# Microcontroller.net
KiCad netlist of a schematic drawn in Altium Designer
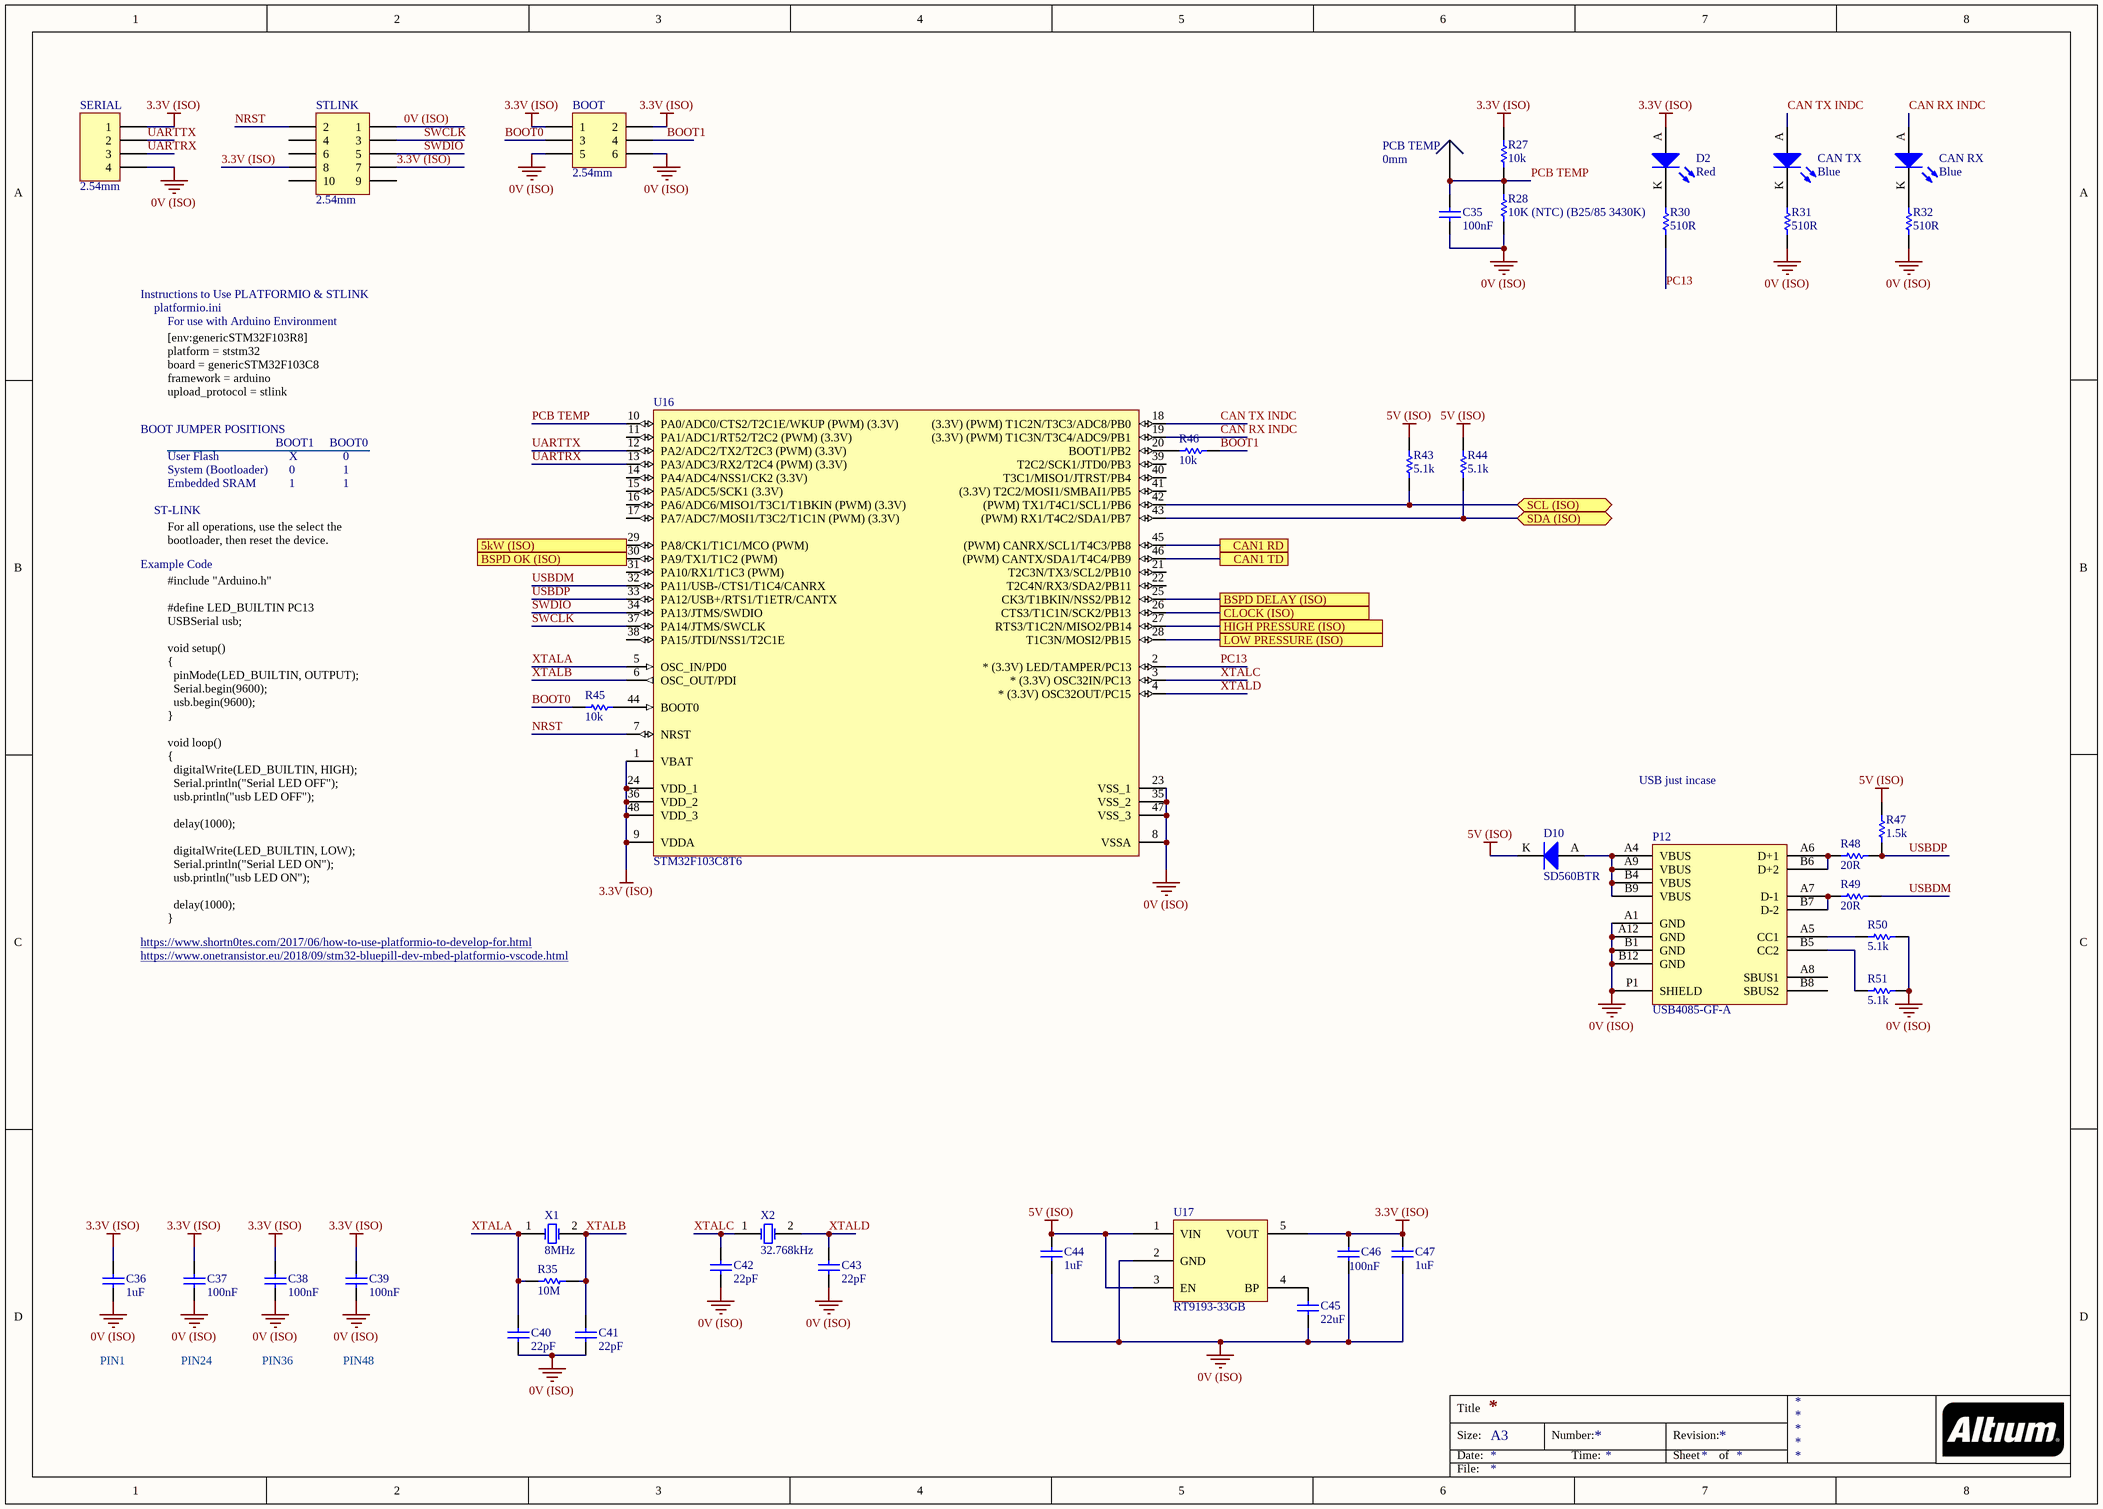
[diagram p0: Microcontroller.SchDoc]

(export (version "E")
  (design (tool "Eeschema 10.0.6"))
  (components
    (comp (ref "BOOT")
      (value "2.54mm")
      (footprint "TH 2.54mm Header 2x3")
      (fields (field (name "PART NUMBER") "TH 2.54mm Header 2x3") (field (name "CONTACT") "NA"))
      (libsource (lib "ts_20-standard-connectors") (part "Header 2x3"))
    )
    (comp (ref "C35")
      (value "100nF")
      (footprint "0805")
      (fields
        (field (name "PART NUMBER") "GCM21BR71E104KA37L")
        (field (name "TOLERANCE") "10%")
        (field (name "MANUFACTURER") "muRata")
      )
      (libsource (lib "ts_20-standard-library") (part "Capacitor"))
    )
    (comp (ref "C36")
      (value "1uF")
      (footprint "0805")
      (fields
        (field (name "PART NUMBER") "AC0805KKX7R8BB105")
        (field (name "TOLERANCE") "10%")
        (field (name "MANUFACTURER") "YAGEO")
      )
      (libsource (lib "ts_20-standard-library") (part "Capacitor"))
    )
    (comp (ref "C37")
      (value "100nF")
      (footprint "0805")
      (fields
        (field (name "PART NUMBER") "GCM21BR71E104KA37L")
        (field (name "TOLERANCE") "10%")
        (field (name "MANUFACTURER") "muRata")
      )
      (libsource (lib "ts_20-standard-library") (part "Capacitor"))
    )
    (comp (ref "C38")
      (value "100nF")
      (footprint "0805")
      (fields
        (field (name "PART NUMBER") "GCM21BR71E104KA37L")
        (field (name "TOLERANCE") "10%")
        (field (name "MANUFACTURER") "muRata")
      )
      (libsource (lib "ts_20-standard-library") (part "Capacitor"))
    )
    (comp (ref "C39")
      (value "100nF")
      (footprint "0805")
      (fields
        (field (name "PART NUMBER") "GCM21BR71E104KA37L")
        (field (name "TOLERANCE") "10%")
        (field (name "MANUFACTURER") "muRata")
      )
      (libsource (lib "ts_20-standard-library") (part "Capacitor"))
    )
    (comp (ref "C40")
      (value "22pF")
      (footprint "0805")
      (fields
        (field (name "PART NUMBER") "GCM21B5C1H220JA37L")
        (field (name "TOLERANCE") "5%")
        (field (name "MANUFACTURER") "muRata")
      )
      (libsource (lib "ts_20-standard-library") (part "Capacitor"))
    )
    (comp (ref "C41")
      (value "22pF")
      (footprint "0805")
      (fields
        (field (name "PART NUMBER") "GCM21B5C1H220JA37L")
        (field (name "TOLERANCE") "5%")
        (field (name "MANUFACTURER") "muRata")
      )
      (libsource (lib "ts_20-standard-library") (part "Capacitor"))
    )
    (comp (ref "C42")
      (value "22pF")
      (footprint "0805")
      (fields
        (field (name "PART NUMBER") "GCM21B5C1H220JA37L")
        (field (name "TOLERANCE") "5%")
        (field (name "MANUFACTURER") "muRata")
      )
      (libsource (lib "ts_20-standard-library") (part "Capacitor"))
    )
    (comp (ref "C43")
      (value "22pF")
      (footprint "0805")
      (fields
        (field (name "PART NUMBER") "GCM21B5C1H220JA37L")
        (field (name "TOLERANCE") "5%")
        (field (name "MANUFACTURER") "muRata")
      )
      (libsource (lib "ts_20-standard-library") (part "Capacitor"))
    )
    (comp (ref "C44")
      (value "1uF")
      (footprint "0805")
      (fields
        (field (name "PART NUMBER") "AC0805KKX7R8BB105")
        (field (name "TOLERANCE") "10%")
        (field (name "MANUFACTURER") "YAGEO")
      )
      (libsource (lib "ts_20-standard-library") (part "Capacitor"))
    )
    (comp (ref "C45")
      (value "22uF")
      (footprint "0805")
      (fields
        (field (name "PART NUMBER") "GRM21BR61A226ME51L")
        (field (name "TOLERANCE") "20%")
        (field (name "MANUFACTURER") "muRata")
      )
      (libsource (lib "ts_20-standard-library") (part "Capacitor"))
    )
    (comp (ref "C46")
      (value "100nF")
      (footprint "0805")
      (fields
        (field (name "PART NUMBER") "GCM21BR71E104KA37L")
        (field (name "TOLERANCE") "10%")
        (field (name "MANUFACTURER") "muRata")
      )
      (libsource (lib "ts_20-standard-library") (part "Capacitor"))
    )
    (comp (ref "C47")
      (value "1uF")
      (footprint "0805")
      (fields
        (field (name "PART NUMBER") "AC0805KKX7R8BB105")
        (field (name "TOLERANCE") "10%")
        (field (name "MANUFACTURER") "YAGEO")
      )
      (libsource (lib "ts_20-standard-library") (part "Capacitor"))
    )
    (comp (ref "CAN RX")
      (value "Blue")
      (footprint "0805 LED")
      (description "LED BLUE CLEAR 2012 SMD")
      (fields
        (field (name "PART NUMBER") "SML-MN2BCTT86C")
        (field (name "MANUFACTURER") "ROHM Semiconductor")
      )
      (libsource (lib "ts_20-standard-library") (part "LED"))
    )
    (comp (ref "CAN TX")
      (value "Blue")
      (footprint "0805 LED")
      (description "LED BLUE CLEAR 2012 SMD")
      (fields
        (field (name "PART NUMBER") "SML-MN2BCTT86C")
        (field (name "MANUFACTURER") "ROHM Semiconductor")
      )
      (libsource (lib "ts_20-standard-library") (part "LED"))
    )
    (comp (ref "D2")
      (value "Red")
      (footprint "0805 LED")
      (description "Red LED Indication - Discrete 1.75V 0805 (2012 Metric)")
      (fields (field (name "PART NUMBER") "SML-210LTT86") (field (name "MANUFACTURER") "ROHM Semiconductor"))
      (libsource (lib "ts_20-standard-library") (part "LED"))
    )
    (comp (ref "D10")
      (value "SD560BTR")
      (footprint "SMB Diode")
      (description "1.2V_F 600V 5A SMB")
      (fields
        (field (name "MANUFACTURER") "SMC Diode Solutions")
        (field (name "DIGIKEY PART NUMBER") "1655-1530-2-ND")
      )
      (libsource (lib "ts_20-standard-library") (part "Diode"))
    )
    (comp (ref "P12")
      (value "USB4085-GF-A")
      (footprint "USB4085-GF-A")
      (description "USB - C (Type - C) USB 2.0 Receptacle Connector 16 Position Through Hole, Right Angle")
      (fields (field (name "DIGIKEY PART NUMBER") "2073-USB4085-GF-ACT-ND"))
      (libsource (lib "ts_20-standard-connectors") (part "USB4085-GF-A"))
    )
    (comp (ref "PCB TEMP")
      (value "0mm")
      (footprint "SMD Test Point")
      (fields (field (name "PART NUMBER") "SMD Test Point") (field (name "CONTACT") "NA"))
      (libsource (lib "ts_20-standard-connectors") (part "Test Point"))
    )
    (comp (ref "R27")
      (value "10k")
      (footprint "0805")
      (fields
        (field (name "PART NUMBER") "RC0805FR0710KL")
        (field (name "MANUFACTURER") "YAGEO")
        (field (name "TOLERANCE") "0.01")
      )
      (libsource (lib "ts_20-standard-library") (part "Resistor"))
    )
    (comp (ref "R28")
      (value "10K (NTC) (B25/85 3430K)")
      (footprint "0805")
      (fields
        (field (name "PART NUMBER") "NTCS0805E3103FLT")
        (field (name "MANUFACTURER") "Vishay Beyschlag")
        (field (name "TOLERANCE") "0.01")
      )
      (libsource (lib "ts_20-standard-library") (part "Resistor"))
    )
    (comp (ref "R30")
      (value "510R")
      (footprint "0805")
      (fields
        (field (name "PART NUMBER") "RC0805FR07510RL")
        (field (name "MANUFACTURER") "YAGEO")
        (field (name "TOLERANCE") "0.01")
      )
      (libsource (lib "ts_20-standard-library") (part "Resistor"))
    )
    (comp (ref "R31")
      (value "510R")
      (footprint "0805")
      (fields
        (field (name "PART NUMBER") "RC0805FR07510RL")
        (field (name "MANUFACTURER") "YAGEO")
        (field (name "TOLERANCE") "0.01")
      )
      (libsource (lib "ts_20-standard-library") (part "Resistor"))
    )
    (comp (ref "R32")
      (value "510R")
      (footprint "0805")
      (fields
        (field (name "PART NUMBER") "RC0805FR07510RL")
        (field (name "MANUFACTURER") "YAGEO")
        (field (name "TOLERANCE") "0.01")
      )
      (libsource (lib "ts_20-standard-library") (part "Resistor"))
    )
    (comp (ref "R35")
      (value "10M")
      (footprint "0805")
      (fields
        (field (name "PART NUMBER") "RC0805FR0710ML")
        (field (name "MANUFACTURER") "YAGEO")
        (field (name "TOLERANCE") "0.01")
      )
      (libsource (lib "ts_20-standard-library") (part "Resistor"))
    )
    (comp (ref "R43")
      (value "5.1k")
      (footprint "0805")
      (fields
        (field (name "PART NUMBER") "RC0805FR075K1L")
        (field (name "MANUFACTURER") "YAGEO")
        (field (name "TOLERANCE") "0.01")
      )
      (libsource (lib "ts_20-standard-library") (part "Resistor"))
    )
    (comp (ref "R44")
      (value "5.1k")
      (footprint "0805")
      (fields
        (field (name "PART NUMBER") "RC0805FR075K1L")
        (field (name "MANUFACTURER") "YAGEO")
        (field (name "TOLERANCE") "0.01")
      )
      (libsource (lib "ts_20-standard-library") (part "Resistor"))
    )
    (comp (ref "R45")
      (value "10k")
      (footprint "0805")
      (fields
        (field (name "PART NUMBER") "RC0805FR0710KL")
        (field (name "MANUFACTURER") "YAGEO")
        (field (name "TOLERANCE") "0.01")
      )
      (libsource (lib "ts_20-standard-library") (part "Resistor"))
    )
    (comp (ref "R46")
      (value "10k")
      (footprint "0805")
      (fields
        (field (name "PART NUMBER") "RC0805FR0710KL")
        (field (name "MANUFACTURER") "YAGEO")
        (field (name "TOLERANCE") "0.01")
      )
      (libsource (lib "ts_20-standard-library") (part "Resistor"))
    )
    (comp (ref "R47")
      (value "1.5k")
      (footprint "0805")
      (fields
        (field (name "PART NUMBER") "RC0805FR071K5L")
        (field (name "MANUFACTURER") "YAGEO")
        (field (name "TOLERANCE") "0.01")
      )
      (libsource (lib "ts_20-standard-library") (part "Resistor"))
    )
    (comp (ref "R48")
      (value "20R")
      (footprint "0805")
      (fields
        (field (name "PART NUMBER") "RC0805FR0720RL")
        (field (name "MANUFACTURER") "YAGEO")
        (field (name "TOLERANCE") "0.01")
      )
      (libsource (lib "ts_20-standard-library") (part "Resistor"))
    )
    (comp (ref "R49")
      (value "20R")
      (footprint "0805")
      (fields
        (field (name "PART NUMBER") "RC0805FR0720RL")
        (field (name "MANUFACTURER") "YAGEO")
        (field (name "TOLERANCE") "0.01")
      )
      (libsource (lib "ts_20-standard-library") (part "Resistor"))
    )
    (comp (ref "R50")
      (value "5.1k")
      (footprint "0805")
      (fields
        (field (name "PART NUMBER") "RC0805FR075K1L")
        (field (name "MANUFACTURER") "YAGEO")
        (field (name "TOLERANCE") "0.01")
      )
      (libsource (lib "ts_20-standard-library") (part "Resistor"))
    )
    (comp (ref "R51")
      (value "5.1k")
      (footprint "0805")
      (fields
        (field (name "PART NUMBER") "RC0805FR075K1L")
        (field (name "MANUFACTURER") "YAGEO")
        (field (name "TOLERANCE") "0.01")
      )
      (libsource (lib "ts_20-standard-library") (part "Resistor"))
    )
    (comp (ref "SERIAL")
      (value "2.54mm")
      (footprint "TH 2.54mm Header 1x4")
      (fields (field (name "PART NUMBER") "TH 2.54mm Header 1x4") (field (name "CONTACT") "NA"))
      (libsource (lib "ts_20-standard-connectors") (part "Header 1x4"))
    )
    (comp (ref "STLINK")
      (value "2.54mm")
      (footprint "TH 2.54mm Header 2x5")
      (fields (field (name "PART NUMBER") "TH 2.54mm Header 2x5") (field (name "CONTACT") "NA"))
      (libsource (lib "ts_20-standard-connectors") (part "Header 2x5"))
    )
    (comp (ref "U16")
      (value "STM32F103C8T6")
      (footprint "STM 48-LQFP")
      (description "ARM® Cortex®-M3 STM32F1 Microcontroller IC 32-Bit 72MHz 64KB (64K x 8) FLASH")
      (fields
        (field (name "MANUFACTURER") "STMicroelectronics")
        (field (name "DIGIKEY PART NUMBER") "497-6063-ND")
      )
      (libsource (lib "ts_20-standard-library") (part "STM32F103C8T6"))
    )
    (comp (ref "U17")
      (value "RT9193-33GB")
      (footprint "RICHTEK SOT-23-5")
      (description "IC REG LINEAR 3.3V 300MA SOT23-5")
      (fields (field (name "MANUFACTURER") "Richtek") (field (name "DIGIKEY PART NUMBER") "1028-1014-1-ND"))
      (libsource (lib "ts_20-standard-library") (part "RT9193-33GB"))
    )
    (comp (ref "X1")
      (value "8MHz")
      (footprint "Abracon HC-49/US")
      (fields
        (field (name "PART NUMBER") "ABLS-8.000MHZ-B4-T")
        (field (name "MANUFACTURER") "Abracon LLC")
        (field (name "DIGIKEY PART NUMBER") "535-10212-2-ND")
      )
      (libsource (lib "ts_20-standard-library") (part "Crystal"))
    )
    (comp (ref "X2")
      (value "32.768kHz")
      (footprint "EPSON 2-SMD")
      (fields
        (field (name "PART NUMBER") "FC-135 32.7680KA-A5")
        (field (name "MANUFACTURER") "EPSON")
        (field (name "DIGIKEY PART NUMBER") "SER4103TR-ND")
      )
      (libsource (lib "ts_20-standard-library") (part "Crystal"))
    )
  )
  (nets
    (net (code "1") (name "/5kW (ISO)") (class "Default")
      (node (ref "U16") (pin "29") (pinfunction "PA8/CK1/T1C1/MCO_(PWM)_29") (pintype "bidirectional"))
    )
    (net (code "2") (name "/BOOT0") (class "Default")
      (node (ref "BOOT") (pin "3") (pinfunction "3_3") (pintype "passive"))
      (node (ref "R45") (pin "1") (pinfunction "1_1") (pintype "passive"))
    )
    (net (code "3") (name "/BOOT1") (class "Default")
      (node (ref "BOOT") (pin "4") (pinfunction "4_4") (pintype "passive"))
      (node (ref "R46") (pin "2") (pinfunction "2_2") (pintype "passive"))
    )
    (net (code "4") (name "/BSPD DELAY (ISO)") (class "Default")
      (node (ref "U16") (pin "25") (pinfunction "CK3/T1BKIN/NSS2/PB12_25") (pintype "bidirectional"))
    )
    (net (code "5") (name "/BSPD OK (ISO)") (class "Default")
      (node (ref "U16") (pin "30") (pinfunction "PA9/TX1/T1C2_(PWM)_30") (pintype "bidirectional"))
    )
    (net (code "6") (name "/CAN RX INDC") (class "Default")
      (node (ref "CAN RX") (pin "A") (pinfunction "A_A") (pintype "passive"))
      (node (ref "U16") (pin "19") (pinfunction "(3.3V)_(PWM)_T1C3N/T3C4/ADC9/PB1_19") (pintype "bidirectional"))
    )
    (net (code "7") (name "/CAN TX INDC") (class "Default")
      (node (ref "CAN TX") (pin "A") (pinfunction "A_A") (pintype "passive"))
      (node (ref "U16") (pin "18") (pinfunction "(3.3V)_(PWM)_T1C2N/T3C3/ADC8/PB0_18") (pintype "bidirectional"))
    )
    (net (code "8") (name "/CAN1 RD") (class "Default")
      (node (ref "U16") (pin "45") (pinfunction "(PWM)_CANRX/SCL1/T4C3/PB8_45") (pintype "bidirectional"))
    )
    (net (code "9") (name "/CAN1 TD") (class "Default")
      (node (ref "U16") (pin "46") (pinfunction "(PWM)_CANTX/SDA1/T4C4/PB9_46") (pintype "bidirectional"))
    )
    (net (code "10") (name "/CLOCK (ISO)") (class "Default")
      (node (ref "U16") (pin "26") (pinfunction "CTS3/T1C1N/SCK2/PB13_26") (pintype "bidirectional"))
    )
    (net (code "11") (name "/HIGH PRESSURE (ISO)") (class "Default")
      (node (ref "U16") (pin "27") (pinfunction "RTS3/T1C2N/MISO2/PB14_27") (pintype "bidirectional"))
    )
    (net (code "12") (name "/LOW PRESSURE (ISO)") (class "Default")
      (node (ref "U16") (pin "28") (pinfunction "T1C3N/MOSI2/PB15_28") (pintype "bidirectional"))
    )
    (net (code "13") (name "/NRST") (class "Default")
      (node (ref "STLINK") (pin "2") (pinfunction "2_2") (pintype "passive"))
      (node (ref "U16") (pin "7") (pinfunction "NRST_7") (pintype "bidirectional"))
    )
    (net (code "14") (name "/PC13") (class "Default")
      (node (ref "R30") (pin "1") (pinfunction "1_1") (pintype "passive"))
      (node (ref "U16") (pin "2") (pinfunction "*_(3.3V)_LED/TAMPER/PC13_2") (pintype "bidirectional"))
    )
    (net (code "15") (name "/PCB TEMP") (class "Default")
      (node (ref "C35") (pin "2") (pinfunction "2_2") (pintype "passive"))
      (node (ref "PCB TEMP") (pin "1") (pinfunction "1_1") (pintype "passive"))
      (node (ref "R27") (pin "1") (pinfunction "1_1") (pintype "passive"))
      (node (ref "R28") (pin "2") (pinfunction "2_2") (pintype "passive"))
      (node (ref "U16") (pin "10") (pinfunction "PA0/ADC0/CTS2/T2C1E/WKUP_(PWM)_(3.3V)_10") (pintype "bidirectional"))
    )
    (net (code "16") (name "/SCL (ISO)") (class "Default")
      (node (ref "R43") (pin "1") (pinfunction "1_1") (pintype "passive"))
      (node (ref "U16") (pin "42") (pinfunction "(PWM)_TX1/T4C1/SCL1/PB6_42") (pintype "bidirectional"))
    )
    (net (code "17") (name "/SDA (ISO)") (class "Default")
      (node (ref "R44") (pin "1") (pinfunction "1_1") (pintype "passive"))
      (node (ref "U16") (pin "43") (pinfunction "(PWM)_RX1/T4C2/SDA1/PB7_43") (pintype "bidirectional"))
    )
    (net (code "18") (name "/SWCLK") (class "Default")
      (node (ref "STLINK") (pin "3") (pinfunction "3_3") (pintype "passive"))
      (node (ref "U16") (pin "37") (pinfunction "PA14/JTMS/SWCLK_37") (pintype "bidirectional"))
    )
    (net (code "19") (name "/SWDIO") (class "Default")
      (node (ref "STLINK") (pin "5") (pinfunction "5_5") (pintype "passive"))
      (node (ref "U16") (pin "34") (pinfunction "PA13/JTMS/SWDIO_34") (pintype "bidirectional"))
    )
    (net (code "20") (name "/UARTRX") (class "Default")
      (node (ref "SERIAL") (pin "3") (pinfunction "3_3") (pintype "passive"))
      (node (ref "U16") (pin "13") (pinfunction "PA3/ADC3/RX2/T2C4_(PWM)_(3.3V)_13") (pintype "bidirectional"))
    )
    (net (code "21") (name "/UARTTX") (class "Default")
      (node (ref "SERIAL") (pin "2") (pinfunction "2_2") (pintype "passive"))
      (node (ref "U16") (pin "12") (pinfunction "PA2/ADC2/TX2/T2C3_(PWM)_(3.3V)_12") (pintype "bidirectional"))
    )
    (net (code "22") (name "/USBDM") (class "Default")
      (node (ref "R49") (pin "2") (pinfunction "2_2") (pintype "passive"))
      (node (ref "U16") (pin "32") (pinfunction "PA11/USB-/CTS1/T1C4/CANRX_32") (pintype "bidirectional"))
    )
    (net (code "23") (name "/USBDP") (class "Default")
      (node (ref "R47") (pin "1") (pinfunction "1_1") (pintype "passive"))
      (node (ref "R48") (pin "2") (pinfunction "2_2") (pintype "passive"))
      (node (ref "U16") (pin "33") (pinfunction "PA12/USB+/RTS1/T1ETR/CANTX_33") (pintype "bidirectional"))
    )
    (net (code "24") (name "/XTALA") (class "Default")
      (node (ref "C40") (pin "2") (pinfunction "2_2") (pintype "passive"))
      (node (ref "R35") (pin "1") (pinfunction "1_1") (pintype "passive"))
      (node (ref "U16") (pin "5") (pinfunction "OSC_IN/PD0_5") (pintype "input"))
      (node (ref "X1") (pin "1") (pinfunction "OSC1_1") (pintype "passive"))
    )
    (net (code "25") (name "/XTALB") (class "Default")
      (node (ref "C41") (pin "2") (pinfunction "2_2") (pintype "passive"))
      (node (ref "R35") (pin "2") (pinfunction "2_2") (pintype "passive"))
      (node (ref "U16") (pin "6") (pinfunction "OSC_OUT/PDI_6") (pintype "output"))
      (node (ref "X1") (pin "2") (pinfunction "OSC2_2") (pintype "passive"))
    )
    (net (code "26") (name "/XTALC") (class "Default")
      (node (ref "C42") (pin "2") (pinfunction "2_2") (pintype "passive"))
      (node (ref "U16") (pin "3") (pinfunction "*_(3.3V)_OSC32IN/PC13_3") (pintype "bidirectional"))
      (node (ref "X2") (pin "1") (pinfunction "OSC1_1") (pintype "passive"))
    )
    (net (code "27") (name "/XTALD") (class "Default")
      (node (ref "C43") (pin "2") (pinfunction "2_2") (pintype "passive"))
      (node (ref "U16") (pin "4") (pinfunction "*_(3.3V)_OSC32OUT/PC15_4") (pintype "bidirectional"))
      (node (ref "X2") (pin "2") (pinfunction "OSC2_2") (pintype "passive"))
    )
    (net (code "28") (name "0V (ISO)") (class "Default")
      (node (ref "BOOT") (pin "5") (pinfunction "5_5") (pintype "passive"))
      (node (ref "BOOT") (pin "6") (pinfunction "6_6") (pintype "passive"))
      (node (ref "C35") (pin "1") (pinfunction "1_1") (pintype "passive"))
      (node (ref "C36") (pin "1") (pinfunction "1_1") (pintype "passive"))
      (node (ref "C37") (pin "1") (pinfunction "1_1") (pintype "passive"))
      (node (ref "C38") (pin "1") (pinfunction "1_1") (pintype "passive"))
      (node (ref "C39") (pin "1") (pinfunction "1_1") (pintype "passive"))
      (node (ref "C40") (pin "1") (pinfunction "1_1") (pintype "passive"))
      (node (ref "C41") (pin "1") (pinfunction "1_1") (pintype "passive"))
      (node (ref "C42") (pin "1") (pinfunction "1_1") (pintype "passive"))
      (node (ref "C43") (pin "1") (pinfunction "1_1") (pintype "passive"))
      (node (ref "C44") (pin "1") (pinfunction "1_1") (pintype "passive"))
      (node (ref "C45") (pin "1") (pinfunction "1_1") (pintype "passive"))
      (node (ref "C46") (pin "1") (pinfunction "1_1") (pintype "passive"))
      (node (ref "C47") (pin "1") (pinfunction "1_1") (pintype "passive"))
      (node (ref "P12") (pin "A1") (pinfunction "GND_A1") (pintype "passive"))
      (node (ref "P12") (pin "A12") (pinfunction "GND_A12") (pintype "passive"))
      (node (ref "P12") (pin "B1") (pinfunction "GND_B1") (pintype "passive"))
      (node (ref "P12") (pin "B12") (pinfunction "GND_B12") (pintype "passive"))
      (node (ref "P12") (pin "P1") (pinfunction "SHIELD_P1") (pintype "passive"))
      (node (ref "R28") (pin "1") (pinfunction "1_1") (pintype "passive"))
      (node (ref "R31") (pin "1") (pinfunction "1_1") (pintype "passive"))
      (node (ref "R32") (pin "1") (pinfunction "1_1") (pintype "passive"))
      (node (ref "R50") (pin "2") (pinfunction "2_2") (pintype "passive"))
      (node (ref "R51") (pin "2") (pinfunction "2_2") (pintype "passive"))
      (node (ref "SERIAL") (pin "4") (pinfunction "4_4") (pintype "passive"))
      (node (ref "STLINK") (pin "1") (pinfunction "1_1") (pintype "passive"))
      (node (ref "U16") (pin "23") (pinfunction "VSS_1_23") (pintype "power_in"))
      (node (ref "U16") (pin "35") (pinfunction "VSS_2_35") (pintype "power_in"))
      (node (ref "U16") (pin "47") (pinfunction "VSS_3_47") (pintype "power_in"))
      (node (ref "U16") (pin "8") (pinfunction "VSSA_8") (pintype "power_in"))
      (node (ref "U17") (pin "2") (pinfunction "GND_2") (pintype "passive"))
    )
    (net (code "29") (name "3.3V (ISO)") (class "Default")
      (node (ref "BOOT") (pin "1") (pinfunction "1_1") (pintype "passive"))
      (node (ref "BOOT") (pin "2") (pinfunction "2_2") (pintype "passive"))
      (node (ref "C36") (pin "2") (pinfunction "2_2") (pintype "passive"))
      (node (ref "C37") (pin "2") (pinfunction "2_2") (pintype "passive"))
      (node (ref "C38") (pin "2") (pinfunction "2_2") (pintype "passive"))
      (node (ref "C39") (pin "2") (pinfunction "2_2") (pintype "passive"))
      (node (ref "C46") (pin "2") (pinfunction "2_2") (pintype "passive"))
      (node (ref "C47") (pin "2") (pinfunction "2_2") (pintype "passive"))
      (node (ref "D2") (pin "A") (pinfunction "A_A") (pintype "passive"))
      (node (ref "R27") (pin "2") (pinfunction "2_2") (pintype "passive"))
      (node (ref "SERIAL") (pin "1") (pinfunction "1_1") (pintype "passive"))
      (node (ref "STLINK") (pin "7") (pinfunction "7_7") (pintype "passive"))
      (node (ref "STLINK") (pin "8") (pinfunction "8_8") (pintype "passive"))
      (node (ref "U16") (pin "1") (pinfunction "VBAT_1") (pintype "power_in"))
      (node (ref "U16") (pin "24") (pinfunction "VDD_1_24") (pintype "power_in"))
      (node (ref "U16") (pin "36") (pinfunction "VDD_2_36") (pintype "power_in"))
      (node (ref "U16") (pin "48") (pinfunction "VDD_3_48") (pintype "power_in"))
      (node (ref "U16") (pin "9") (pinfunction "VDDA_9") (pintype "power_in"))
      (node (ref "U17") (pin "5") (pinfunction "VOUT_5") (pintype "passive"))
    )
    (net (code "30") (name "5V (ISO)") (class "Default")
      (node (ref "C44") (pin "2") (pinfunction "2_2") (pintype "passive"))
      (node (ref "D10") (pin "K") (pinfunction "K_K") (pintype "passive"))
      (node (ref "R43") (pin "2") (pinfunction "2_2") (pintype "passive"))
      (node (ref "R44") (pin "2") (pinfunction "2_2") (pintype "passive"))
      (node (ref "R47") (pin "2") (pinfunction "2_2") (pintype "passive"))
      (node (ref "U17") (pin "1") (pinfunction "VIN_1") (pintype "passive"))
      (node (ref "U17") (pin "3") (pinfunction "EN_3") (pintype "passive"))
    )
    (net (code "31") (name "Net-(CAN RX-PadK)") (class "Default")
      (node (ref "CAN RX") (pin "K") (pinfunction "K_K") (pintype "passive"))
      (node (ref "R32") (pin "2") (pinfunction "2_2") (pintype "passive"))
    )
    (net (code "32") (name "Net-(CAN TX-PadK)") (class "Default")
      (node (ref "CAN TX") (pin "K") (pinfunction "K_K") (pintype "passive"))
      (node (ref "R31") (pin "2") (pinfunction "2_2") (pintype "passive"))
    )
    (net (code "33") (name "Net-(D2-PadK)") (class "Default")
      (node (ref "D2") (pin "K") (pinfunction "K_K") (pintype "passive"))
      (node (ref "R30") (pin "2") (pinfunction "2_2") (pintype "passive"))
    )
    (net (code "34") (name "Net-(D10-PadA)") (class "Default")
      (node (ref "D10") (pin "A") (pinfunction "A_A") (pintype "passive"))
      (node (ref "P12") (pin "A4") (pinfunction "VBUS_A4") (pintype "passive"))
      (node (ref "P12") (pin "A9") (pinfunction "VBUS_A9") (pintype "passive"))
      (node (ref "P12") (pin "B4") (pinfunction "VBUS_B4") (pintype "passive"))
      (node (ref "P12") (pin "B9") (pinfunction "VBUS_B9") (pintype "passive"))
    )
    (net (code "35") (name "Net-(P12-CC1)") (class "Default")
      (node (ref "P12") (pin "A5") (pinfunction "CC1_A5") (pintype "passive"))
      (node (ref "R50") (pin "1") (pinfunction "1_1") (pintype "passive"))
    )
    (net (code "36") (name "Net-(P12-CC2)") (class "Default")
      (node (ref "P12") (pin "B5") (pinfunction "CC2_B5") (pintype "passive"))
      (node (ref "R51") (pin "1") (pinfunction "1_1") (pintype "passive"))
    )
    (net (code "37") (name "Net-(P12-D+1)") (class "Default")
      (node (ref "P12") (pin "A6") (pinfunction "D+1_A6") (pintype "passive"))
      (node (ref "P12") (pin "B6") (pinfunction "D+2_B6") (pintype "passive"))
      (node (ref "R48") (pin "1") (pinfunction "1_1") (pintype "passive"))
    )
    (net (code "38") (name "Net-(P12-D-1)") (class "Default")
      (node (ref "P12") (pin "A7") (pinfunction "D-1_A7") (pintype "passive"))
      (node (ref "P12") (pin "B7") (pinfunction "D-2_B7") (pintype "passive"))
      (node (ref "R49") (pin "1") (pinfunction "1_1") (pintype "passive"))
    )
    (net (code "39") (name "Net-(U16-BOOT0)") (class "Default")
      (node (ref "R45") (pin "2") (pinfunction "2_2") (pintype "passive"))
      (node (ref "U16") (pin "44") (pinfunction "BOOT0_44") (pintype "input"))
    )
    (net (code "40") (name "Net-(U16-BOOT1{slash}PB2)") (class "Default")
      (node (ref "R46") (pin "1") (pinfunction "1_1") (pintype "passive"))
      (node (ref "U16") (pin "20") (pinfunction "BOOT1/PB2_20") (pintype "bidirectional"))
    )
    (net (code "41") (name "Net-(U17-BP)") (class "Default")
      (node (ref "C45") (pin "2") (pinfunction "2_2") (pintype "passive"))
      (node (ref "U17") (pin "4") (pinfunction "BP_4") (pintype "passive"))
    )
    (net (code "42") (name "unconnected-(P12-SBUS1-PadA8)") (class "Default")
      (node (ref "P12") (pin "A8") (pinfunction "SBUS1_A8") (pintype "passive"))
    )
    (net (code "43") (name "unconnected-(P12-SBUS2-PadB8)") (class "Default")
      (node (ref "P12") (pin "B8") (pinfunction "SBUS2_B8") (pintype "passive"))
    )
    (net (code "44") (name "unconnected-(STLINK-Pad4)") (class "Default")
      (node (ref "STLINK") (pin "4") (pinfunction "4_4") (pintype "passive"))
    )
    (net (code "45") (name "unconnected-(STLINK-Pad6)") (class "Default")
      (node (ref "STLINK") (pin "6") (pinfunction "6_6") (pintype "passive"))
    )
    (net (code "46") (name "unconnected-(STLINK-Pad9)") (class "Default")
      (node (ref "STLINK") (pin "9") (pinfunction "9_9") (pintype "passive"))
    )
    (net (code "47") (name "unconnected-(STLINK-Pad10)") (class "Default")
      (node (ref "STLINK") (pin "10") (pinfunction "10_10") (pintype "passive"))
    )
    (net (code "48") (name "unconnected-(U16-(3.3V)_T2C2{slash}MOSI1{slash}SMBAI1{slash}PB5-Pad41)") (class "Default")
      (node (ref "U16") (pin "41") (pinfunction "(3.3V)_T2C2/MOSI1/SMBAI1/PB5_41") (pintype "bidirectional"))
    )
    (net (code "49") (name "unconnected-(U16-PA1{slash}ADC1{slash}RT52{slash}T2C2_(PWM)_(3.3V)-Pad11)") (class "Default")
      (node (ref "U16") (pin "11") (pinfunction "PA1/ADC1/RT52/T2C2_(PWM)_(3.3V)_11") (pintype "bidirectional"))
    )
    (net (code "50") (name "unconnected-(U16-PA4{slash}ADC4{slash}NSS1{slash}CK2_(3.3V)-Pad14)") (class "Default")
      (node (ref "U16") (pin "14") (pinfunction "PA4/ADC4/NSS1/CK2_(3.3V)_14") (pintype "bidirectional"))
    )
    (net (code "51") (name "unconnected-(U16-PA5{slash}ADC5{slash}SCK1_(3.3V)-Pad15)") (class "Default")
      (node (ref "U16") (pin "15") (pinfunction "PA5/ADC5/SCK1_(3.3V)_15") (pintype "bidirectional"))
    )
    (net (code "52") (name "unconnected-(U16-PA6{slash}ADC6{slash}MISO1{slash}T3C1{slash}T1BKIN_(PWM)_(3.3V)-Pad16)") (class "Default")
      (node (ref "U16") (pin "16") (pinfunction "PA6/ADC6/MISO1/T3C1/T1BKIN_(PWM)_(3.3V)_16") (pintype "bidirectional"))
    )
    (net (code "53") (name "unconnected-(U16-PA7{slash}ADC7{slash}MOSI1{slash}T3C2{slash}T1C1N_(PWM)_(3.3V)-Pad17)") (class "Default")
      (node (ref "U16") (pin "17") (pinfunction "PA7/ADC7/MOSI1/T3C2/T1C1N_(PWM)_(3.3V)_17") (pintype "bidirectional"))
    )
    (net (code "54") (name "unconnected-(U16-PA10{slash}RX1{slash}T1C3_(PWM)-Pad31)") (class "Default")
      (node (ref "U16") (pin "31") (pinfunction "PA10/RX1/T1C3_(PWM)_31") (pintype "bidirectional"))
    )
    (net (code "55") (name "unconnected-(U16-PA15{slash}JTDI{slash}NSS1{slash}T2C1E-Pad38)") (class "Default")
      (node (ref "U16") (pin "38") (pinfunction "PA15/JTDI/NSS1/T2C1E_38") (pintype "bidirectional"))
    )
    (net (code "56") (name "unconnected-(U16-T2C2{slash}SCK1{slash}JTD0{slash}PB3-Pad39)") (class "Default")
      (node (ref "U16") (pin "39") (pinfunction "T2C2/SCK1/JTD0/PB3_39") (pintype "bidirectional"))
    )
    (net (code "57") (name "unconnected-(U16-T2C3N{slash}TX3{slash}SCL2{slash}PB10-Pad21)") (class "Default")
      (node (ref "U16") (pin "21") (pinfunction "T2C3N/TX3/SCL2/PB10_21") (pintype "bidirectional"))
    )
    (net (code "58") (name "unconnected-(U16-T2C4N{slash}RX3{slash}SDA2{slash}PB11-Pad22)") (class "Default")
      (node (ref "U16") (pin "22") (pinfunction "T2C4N/RX3/SDA2/PB11_22") (pintype "bidirectional"))
    )
    (net (code "59") (name "unconnected-(U16-T3C1{slash}MISO1{slash}JTRST{slash}PB4-Pad40)") (class "Default")
      (node (ref "U16") (pin "40") (pinfunction "T3C1/MISO1/JTRST/PB4_40") (pintype "bidirectional"))
    )
  )
)
